# Transmitter.net
KiCad netlist of a schematic drawn in Altium Designer
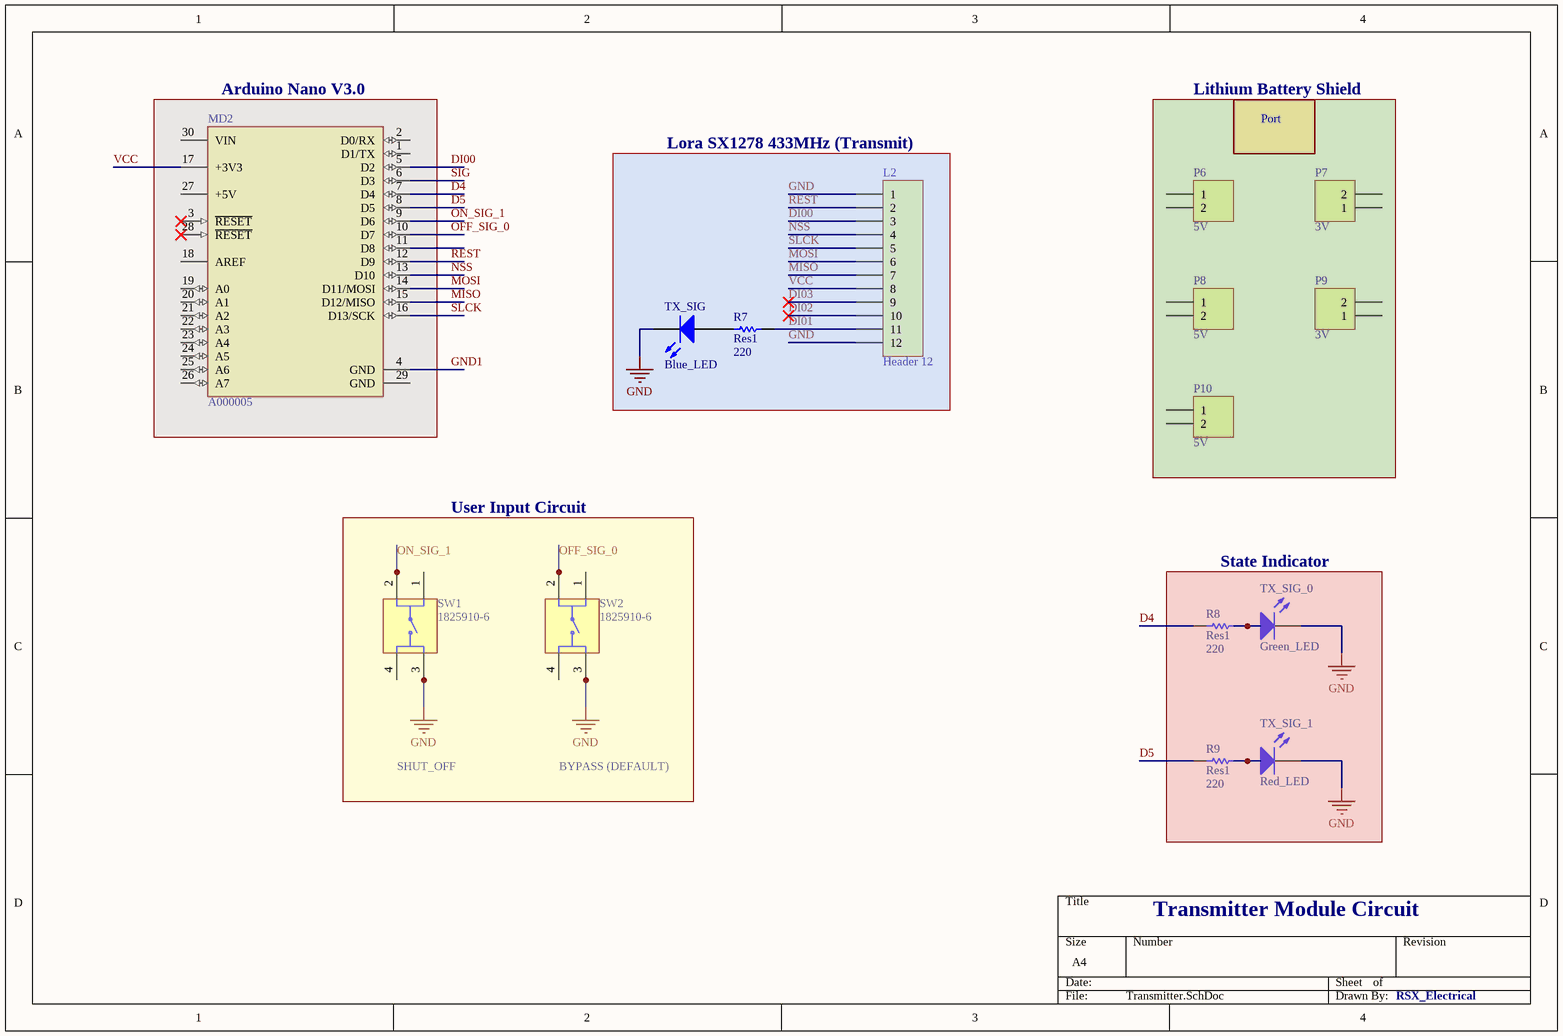
[diagram p0: Transmitter.SchDoc]

(export (version "E")
  (design (tool "Eeschema 10.0.6"))
  (components
    (comp (ref "L2")
      (value "Header 12")
      (footprint "HDR1X12")
      (description "Header, 12-Pin")
      (fields (field (name "PUBLISHER") "Altium Limited"))
      (libsource (lib "Miscellaneous Connectors") (part "Header 12"))
    )
    (comp (ref "MD2")
      (value "A000005")
      (footprint "FP-A000005-MFG")
      (description "ARDUINO NANO ATMEGA328 EVAL BRD")
      (libsource (lib "Altium Content Vault") (part "d190c066e99afd1c6882cf92e11b2cc"))
    )
    (comp (ref "P6")
      (value "5V")
      (footprint "HDR1X2")
      (description "Header, 2-Pin")
      (fields (field (name "PUBLISHER") "Altium Limited"))
      (libsource (lib "Miscellaneous Connectors") (part "Header 2"))
    )
    (comp (ref "P7")
      (value "3V")
      (footprint "HDR1X2")
      (description "Header, 2-Pin")
      (fields (field (name "PUBLISHER") "Altium Limited"))
      (libsource (lib "") (part "Header 2_1"))
    )
    (comp (ref "P8")
      (value "5V")
      (footprint "HDR1X2")
      (description "Header, 2-Pin")
      (fields (field (name "PUBLISHER") "Altium Limited"))
      (libsource (lib "Miscellaneous Connectors") (part "Header 2"))
    )
    (comp (ref "P9")
      (value "3V")
      (footprint "HDR1X2")
      (description "Header, 2-Pin")
      (fields (field (name "PUBLISHER") "Altium Limited"))
      (libsource (lib "") (part "Header 2_1"))
    )
    (comp (ref "P10")
      (value "5V")
      (footprint "HDR1X2")
      (description "Header, 2-Pin")
      (fields (field (name "PUBLISHER") "Altium Limited"))
      (libsource (lib "Miscellaneous Connectors") (part "Header 2"))
    )
    (comp (ref "R7")
      (value "Res1")
      (footprint "AXIAL-0.3")
      (description "Resistor")
      (fields (field (name "ALTIUM_VALUE") "220") (field (name "PUBLISHER") "Altium Limited"))
      (libsource (lib "Miscellaneous Devices") (part "Res1"))
    )
    (comp (ref "R8")
      (value "Res1")
      (footprint "AXIAL-0.3")
      (description "Resistor")
      (fields (field (name "ALTIUM_VALUE") "220") (field (name "PUBLISHER") "Altium Limited"))
      (libsource (lib "Miscellaneous Devices") (part "Res1"))
    )
    (comp (ref "R9")
      (value "Res1")
      (footprint "AXIAL-0.3")
      (description "Resistor")
      (fields (field (name "ALTIUM_VALUE") "220") (field (name "PUBLISHER") "Altium Limited"))
      (libsource (lib "Miscellaneous Devices") (part "Res1"))
    )
    (comp (ref "SW1")
      (value "1825910-6")
      (footprint "SW_1825910-6-4")
      (description "Switch Tactile OFF (ON) SPST Round Button PC Pins 0.05A 24VDC 100000Cycles 1.57N Thru-Hole Loose")
      (libsource (lib "1825910-6") (part "1825910-6"))
    )
    (comp (ref "SW2")
      (value "1825910-6")
      (footprint "SW_1825910-6-4")
      (description "Switch Tactile OFF (ON) SPST Round Button PC Pins 0.05A 24VDC 100000Cycles 1.57N Thru-Hole Loose")
      (libsource (lib "1825910-6") (part "1825910-6"))
    )
    (comp (ref "TX_SIG")
      (value "Blue_LED")
      (footprint "LED-0")
      (description "Typical INFRARED GaAs LED")
      (fields (field (name "PUBLISHER") "Altium Limited"))
      (libsource (lib "Miscellaneous Devices") (part "LED0"))
    )
    (comp (ref "TX_SIG_0")
      (value "Green_LED")
      (footprint "LED-0")
      (description "Typical INFRARED GaAs LED")
      (fields (field (name "PUBLISHER") "Altium Limited"))
      (libsource (lib "Miscellaneous Devices") (part "LED0"))
    )
    (comp (ref "TX_SIG_1")
      (value "Red_LED")
      (footprint "LED-0")
      (description "Typical INFRARED GaAs LED")
      (fields (field (name "PUBLISHER") "Altium Limited"))
      (libsource (lib "Miscellaneous Devices") (part "LED0"))
    )
  )
  (nets
    (net (code "2") (name "/D4") (class "Default")
      (node (ref "MD2") (pin "7") (pinfunction "D4_7") (pintype "bidirectional"))
      (node (ref "R8") (pin "2") (pinfunction "2_2") (pintype "passive"))
    )
    (net (code "3") (name "/D5") (class "Default")
      (node (ref "MD2") (pin "8") (pinfunction "D5_8") (pintype "bidirectional"))
      (node (ref "R9") (pin "2") (pinfunction "2_2") (pintype "passive"))
    )
    (net (code "4") (name "/DI00") (class "Default")
      (node (ref "L2") (pin "3") (pinfunction "3_3") (pintype "passive"))
      (node (ref "MD2") (pin "5") (pinfunction "D2_5") (pintype "bidirectional"))
    )
    (net (code "5") (name "/DI01") (class "Default")
      (node (ref "L2") (pin "11") (pinfunction "11_11") (pintype "passive"))
      (node (ref "R7") (pin "1") (pinfunction "1_1") (pintype "passive"))
    )
    (net (code "6") (name "/DI02") (class "Default")
      (node (ref "L2") (pin "10") (pinfunction "10_10") (pintype "passive+no_connect"))
    )
    (net (code "7") (name "/DI03") (class "Default")
      (node (ref "L2") (pin "9") (pinfunction "9_9") (pintype "passive+no_connect"))
    )
    (net (code "8") (name "/GND1") (class "Default")
      (node (ref "MD2") (pin "4") (pinfunction "GND_4") (pintype "power_in"))
    )
    (net (code "9") (name "/MISO") (class "Default")
      (node (ref "L2") (pin "7") (pinfunction "7_7") (pintype "passive"))
      (node (ref "MD2") (pin "15") (pinfunction "D12/MISO_15") (pintype "bidirectional"))
    )
    (net (code "10") (name "/MOSI") (class "Default")
      (node (ref "L2") (pin "6") (pinfunction "6_6") (pintype "passive"))
      (node (ref "MD2") (pin "14") (pinfunction "D11/MOSI_14") (pintype "bidirectional"))
    )
    (net (code "11") (name "/NSS") (class "Default")
      (node (ref "L2") (pin "4") (pinfunction "4_4") (pintype "passive"))
      (node (ref "MD2") (pin "13") (pinfunction "D10_13") (pintype "bidirectional"))
    )
    (net (code "12") (name "/OFF_SIG_0") (class "Default")
      (node (ref "MD2") (pin "10") (pinfunction "D7_10") (pintype "bidirectional"))
      (node (ref "SW2") (pin "2") (pinfunction "2_2") (pintype "passive"))
    )
    (net (code "13") (name "/ON_SIG_1") (class "Default")
      (node (ref "MD2") (pin "9") (pinfunction "D6_9") (pintype "bidirectional"))
      (node (ref "SW1") (pin "2") (pinfunction "2_2") (pintype "passive"))
    )
    (net (code "14") (name "/REST") (class "Default")
      (node (ref "L2") (pin "2") (pinfunction "2_2") (pintype "passive"))
      (node (ref "MD2") (pin "12") (pinfunction "D9_12") (pintype "bidirectional"))
    )
    (net (code "15") (name "/SIG") (class "Default")
      (node (ref "MD2") (pin "6") (pinfunction "D3_6") (pintype "bidirectional"))
    )
    (net (code "16") (name "/SLCK") (class "Default")
      (node (ref "L2") (pin "5") (pinfunction "5_5") (pintype "passive"))
      (node (ref "MD2") (pin "16") (pinfunction "D13/SCK_16") (pintype "bidirectional"))
    )
    (net (code "17") (name "/VCC") (class "Default")
      (node (ref "L2") (pin "8") (pinfunction "8_8") (pintype "passive"))
      (node (ref "MD2") (pin "17") (pinfunction "+3V3_17") (pintype "power_in"))
    )
    (net (code "18") (name "GND") (class "Default")
      (node (ref "L2") (pin "1") (pinfunction "1_1") (pintype "passive"))
      (node (ref "L2") (pin "12") (pinfunction "12_12") (pintype "passive"))
      (node (ref "SW1") (pin "3") (pinfunction "3_3") (pintype "passive"))
      (node (ref "SW2") (pin "3") (pinfunction "3_3") (pintype "passive"))
      (node (ref "TX_SIG") (pin "2") (pinfunction "K_2") (pintype "passive"))
      (node (ref "TX_SIG_0") (pin "2") (pinfunction "K_2") (pintype "passive"))
      (node (ref "TX_SIG_1") (pin "2") (pinfunction "K_2") (pintype "passive"))
    )
    (net (code "19") (name "Net-(TX_SIG-A)") (class "Default")
      (node (ref "R7") (pin "2") (pinfunction "2_2") (pintype "passive"))
      (node (ref "TX_SIG") (pin "1") (pinfunction "A_1") (pintype "passive"))
    )
    (net (code "20") (name "Net-(TX_SIG_0-A)") (class "Default")
      (node (ref "R8") (pin "1") (pinfunction "1_1") (pintype "passive"))
      (node (ref "TX_SIG_0") (pin "1") (pinfunction "A_1") (pintype "passive"))
    )
    (net (code "21") (name "Net-(TX_SIG_1-A)") (class "Default")
      (node (ref "R9") (pin "1") (pinfunction "1_1") (pintype "passive"))
      (node (ref "TX_SIG_1") (pin "1") (pinfunction "A_1") (pintype "passive"))
    )
    (net (code "22") (name "unconnected-(MD2-+5V-Pad27)") (class "Default")
      (node (ref "MD2") (pin "27") (pinfunction "+5V_27") (pintype "power_in"))
    )
    (net (code "23") (name "unconnected-(MD2-A0-Pad19)") (class "Default")
      (node (ref "MD2") (pin "19") (pinfunction "A0_19") (pintype "bidirectional"))
    )
    (net (code "24") (name "unconnected-(MD2-A1-Pad20)") (class "Default")
      (node (ref "MD2") (pin "20") (pinfunction "A1_20") (pintype "bidirectional"))
    )
    (net (code "25") (name "unconnected-(MD2-A2-Pad21)") (class "Default")
      (node (ref "MD2") (pin "21") (pinfunction "A2_21") (pintype "bidirectional"))
    )
    (net (code "26") (name "unconnected-(MD2-A3-Pad22)") (class "Default")
      (node (ref "MD2") (pin "22") (pinfunction "A3_22") (pintype "bidirectional"))
    )
    (net (code "27") (name "unconnected-(MD2-A4-Pad23)") (class "Default")
      (node (ref "MD2") (pin "23") (pinfunction "A4_23") (pintype "bidirectional"))
    )
    (net (code "28") (name "unconnected-(MD2-A5-Pad24)") (class "Default")
      (node (ref "MD2") (pin "24") (pinfunction "A5_24") (pintype "bidirectional"))
    )
    (net (code "29") (name "unconnected-(MD2-A6-Pad25)") (class "Default")
      (node (ref "MD2") (pin "25") (pinfunction "A6_25") (pintype "bidirectional"))
    )
    (net (code "30") (name "unconnected-(MD2-A7-Pad26)") (class "Default")
      (node (ref "MD2") (pin "26") (pinfunction "A7_26") (pintype "bidirectional"))
    )
    (net (code "31") (name "unconnected-(MD2-AREF-Pad18)") (class "Default")
      (node (ref "MD2") (pin "18") (pinfunction "AREF_18") (pintype "passive"))
    )
    (net (code "32") (name "unconnected-(MD2-D0{slash}RX-Pad2)") (class "Default")
      (node (ref "MD2") (pin "2") (pinfunction "D0/RX_2") (pintype "bidirectional"))
    )
    (net (code "33") (name "unconnected-(MD2-D1{slash}TX-Pad1)") (class "Default")
      (node (ref "MD2") (pin "1") (pinfunction "D1/TX_1") (pintype "bidirectional"))
    )
    (net (code "34") (name "unconnected-(MD2-D8-Pad11)") (class "Default")
      (node (ref "MD2") (pin "11") (pinfunction "D8_11") (pintype "bidirectional"))
    )
    (net (code "35") (name "unconnected-(MD2-GND-Pad29)") (class "Default")
      (node (ref "MD2") (pin "29") (pinfunction "GND_29") (pintype "power_in"))
    )
    (net (code "36") (name "unconnected-(MD2-VIN-Pad30)") (class "Default")
      (node (ref "MD2") (pin "30") (pinfunction "VIN_30") (pintype "power_in"))
    )
    (net (code "37") (name "unconnected-(MD2-~{RESET}-Pad3)") (class "Default")
      (node (ref "MD2") (pin "3") (pinfunction "~{RESET}_3") (pintype "input+no_connect"))
    )
    (net (code "38") (name "unconnected-(MD2-~{RESET}-Pad28)") (class "Default")
      (node (ref "MD2") (pin "28") (pinfunction "~{RESET}_28") (pintype "input+no_connect"))
    )
    (net (code "39") (name "unconnected-(P6-Pad1)") (class "Default")
      (node (ref "P6") (pin "1") (pinfunction "1_1") (pintype "passive"))
    )
    (net (code "40") (name "unconnected-(P6-Pad2)") (class "Default")
      (node (ref "P6") (pin "2") (pinfunction "2_2") (pintype "passive"))
    )
    (net (code "41") (name "unconnected-(P7-Pad1)") (class "Default")
      (node (ref "P7") (pin "1") (pinfunction "1_1") (pintype "passive"))
    )
    (net (code "42") (name "unconnected-(P7-Pad2)") (class "Default")
      (node (ref "P7") (pin "2") (pinfunction "2_2") (pintype "passive"))
    )
    (net (code "43") (name "unconnected-(P8-Pad1)") (class "Default")
      (node (ref "P8") (pin "1") (pinfunction "1_1") (pintype "passive"))
    )
    (net (code "44") (name "unconnected-(P8-Pad2)") (class "Default")
      (node (ref "P8") (pin "2") (pinfunction "2_2") (pintype "passive"))
    )
    (net (code "45") (name "unconnected-(P9-Pad1)") (class "Default")
      (node (ref "P9") (pin "1") (pinfunction "1_1") (pintype "passive"))
    )
    (net (code "46") (name "unconnected-(P9-Pad2)") (class "Default")
      (node (ref "P9") (pin "2") (pinfunction "2_2") (pintype "passive"))
    )
    (net (code "47") (name "unconnected-(P10-Pad1)") (class "Default")
      (node (ref "P10") (pin "1") (pinfunction "1_1") (pintype "passive"))
    )
    (net (code "48") (name "unconnected-(P10-Pad2)") (class "Default")
      (node (ref "P10") (pin "2") (pinfunction "2_2") (pintype "passive"))
    )
    (net (code "49") (name "unconnected-(SW1-Pad1)") (class "Default")
      (node (ref "SW1") (pin "1") (pinfunction "1_1") (pintype "passive"))
    )
    (net (code "50") (name "unconnected-(SW1-Pad4)") (class "Default")
      (node (ref "SW1") (pin "4") (pinfunction "4_4") (pintype "passive"))
    )
    (net (code "51") (name "unconnected-(SW2-Pad1)") (class "Default")
      (node (ref "SW2") (pin "1") (pinfunction "1_1") (pintype "passive"))
    )
    (net (code "52") (name "unconnected-(SW2-Pad4)") (class "Default")
      (node (ref "SW2") (pin "4") (pinfunction "4_4") (pintype "passive"))
    )
  )
)
